# AKK_V3.net
KiCad netlist of a schematic drawn in Altium Designer
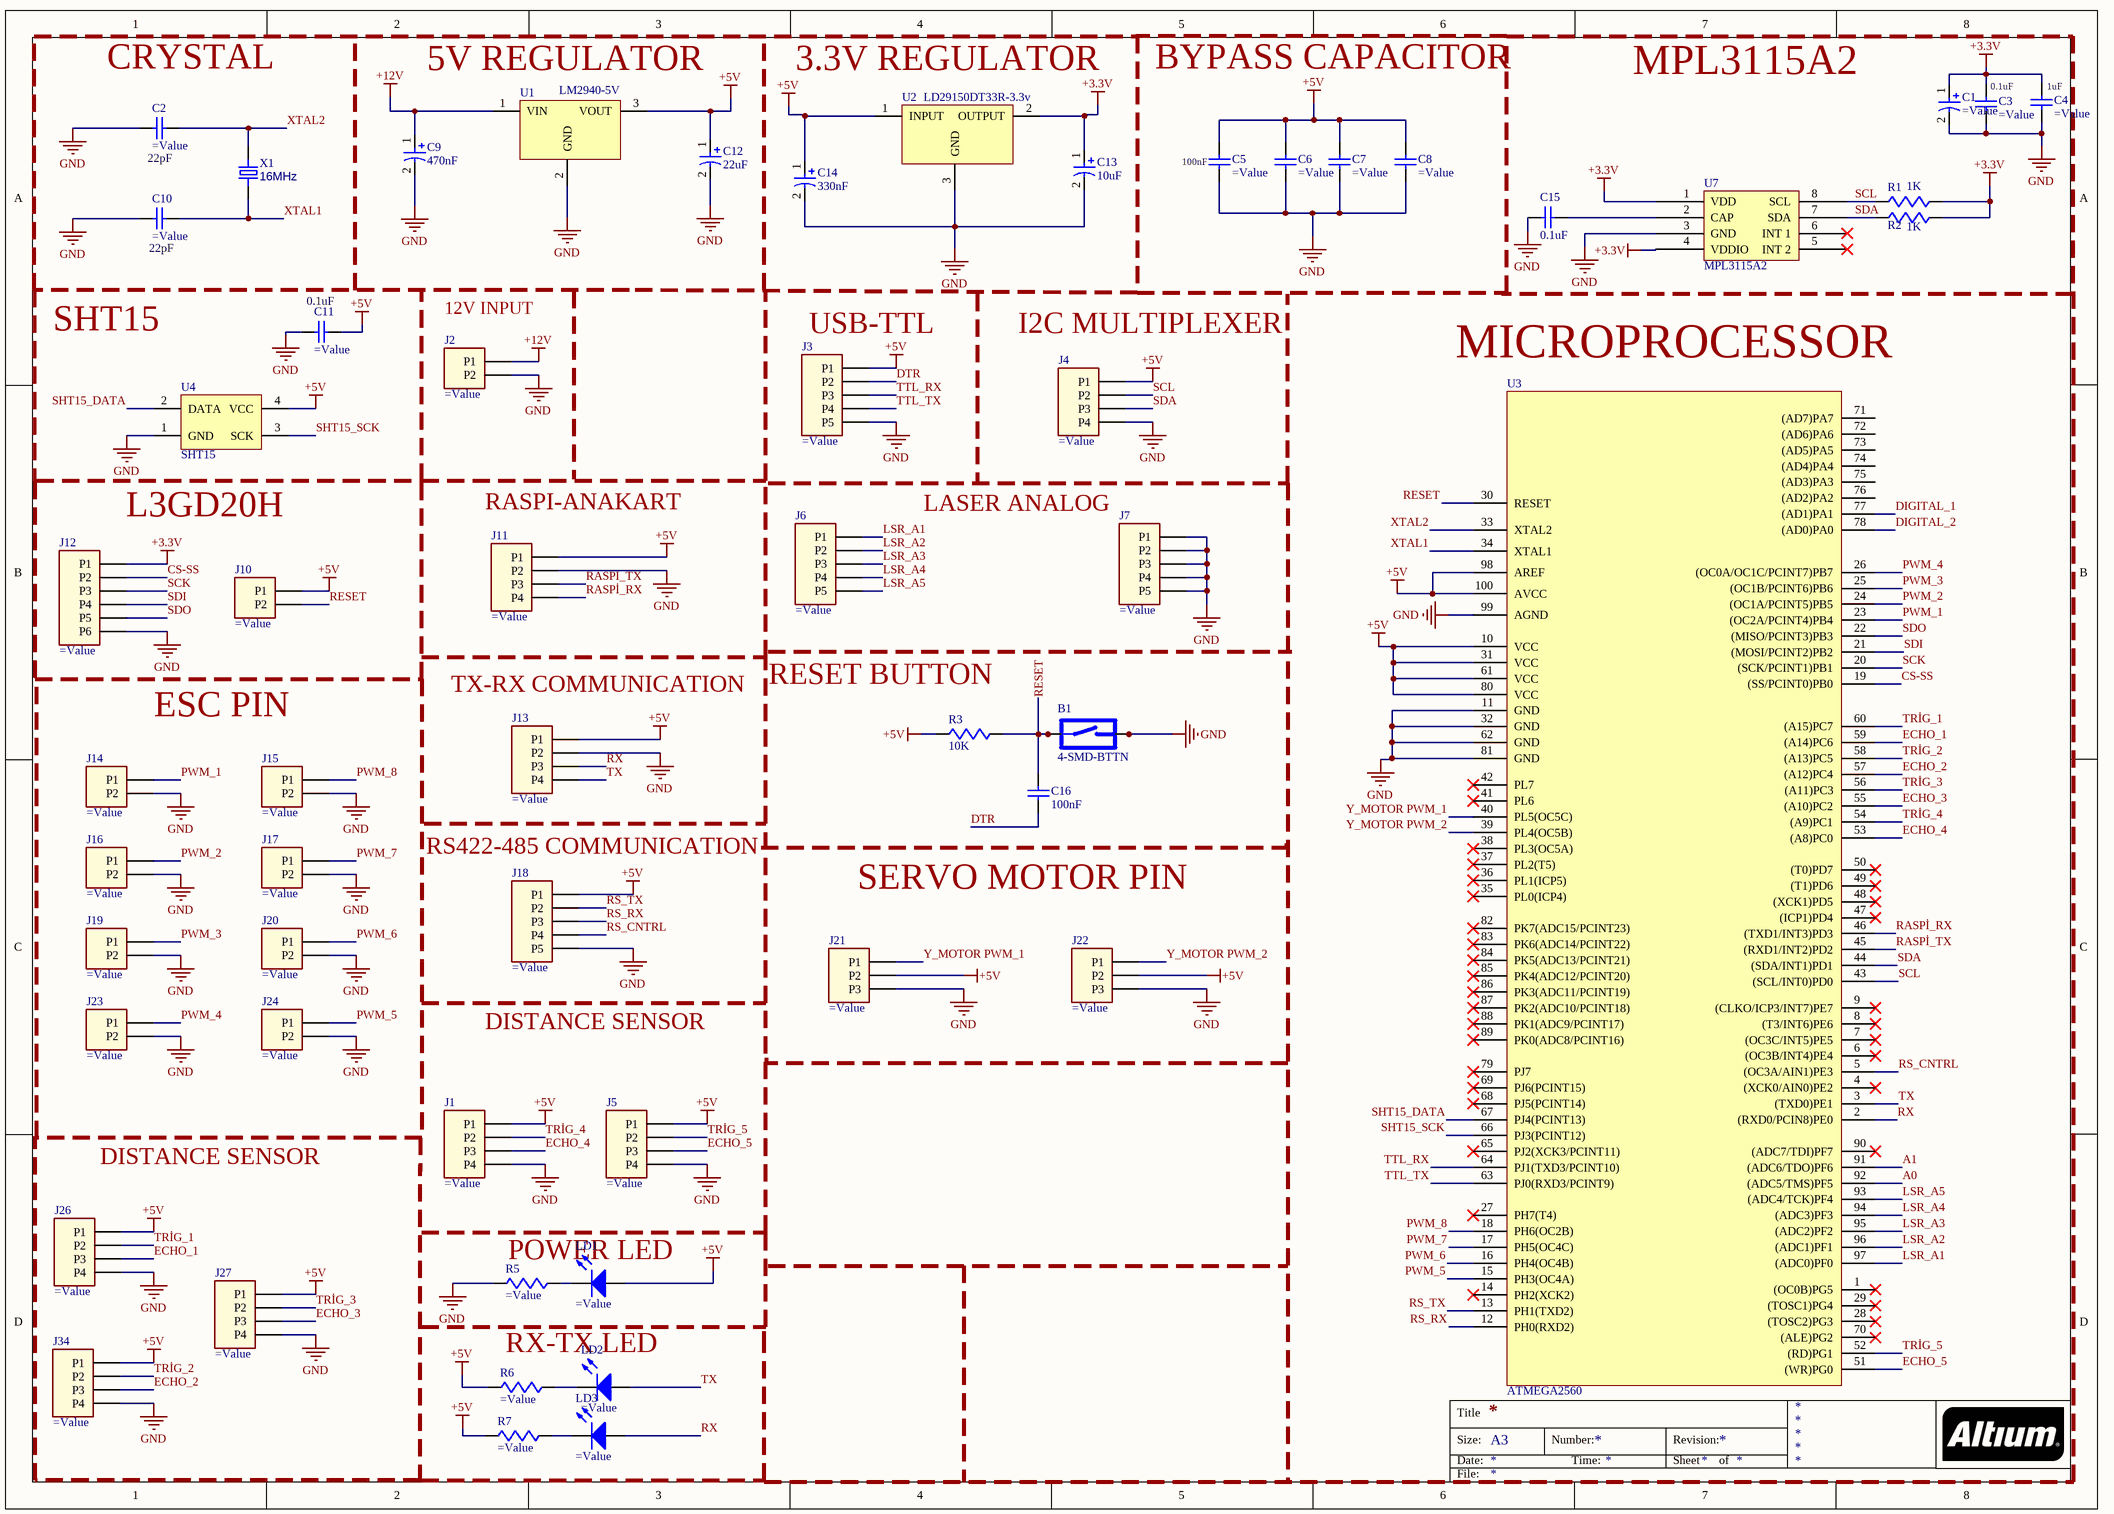
[diagram p0: AKK_V3.SchDoc]

(export (version "E")
  (design (tool "Eeschema 10.0.6"))
  (components
    (comp (ref "B1")
      (value "4-SMD-BTTN")
      (footprint "4-SMD-BTTN-11.6-6.5")
      (description "SWITCH TACTILE SPST-NO 0.05A 24V")
      (fields (field (name "MANUFACTURER PART NUMBER") "B3FS-1012P") (field (name "MANUFACTURER") "Omron"))
      (libsource (lib "MyDatabaseLib") (part "4-SMD-BTTN"))
    )
    (comp (ref "C1")
      (value "~")
      (footprint "CAP_5MM")
      (description "Capacitor; Alum Electrolytic; Cap 10 uF; Tol 20%; Vol-Rtg 16 VDC; SMT; 4x5.5; Cut Tape")
      (fields
        (field (name "MANUFACTURER PART NUMBER") "EEE-1CA100SR")
        (field (name "MANUFACTURER") "Panasonic")
      )
      (libsource (lib "MyDatabaseLib") (part "Capacitor POL"))
    )
    (comp (ref "C2")
      (value "~")
      (footprint "C1206N")
      (description "CAP CER 0.1UF 50V X7R 1206")
      (fields
        (field (name "MANUFACTURER PART NUMBER") "C1206C104K5RAC7210")
        (field (name "MANUFACTURER") "KEMET")
      )
      (libsource (lib "MyDatabaseLib") (part "CapacitorNonPol"))
    )
    (comp (ref "C3")
      (value "~")
      (footprint "C1206N")
      (description "CAP CER 0.1UF 50V X7R 1206")
      (fields
        (field (name "MANUFACTURER PART NUMBER") "C1206C104K5RAC7210")
        (field (name "MANUFACTURER") "KEMET")
      )
      (libsource (lib "MyDatabaseLib") (part "CapacitorNonPol"))
    )
    (comp (ref "C4")
      (value "~")
      (footprint "C1206N")
      (description "CAP CER 0.1UF 50V X7R 1206")
      (fields
        (field (name "MANUFACTURER PART NUMBER") "C1206C104K5RAC7210")
        (field (name "MANUFACTURER") "KEMET")
      )
      (libsource (lib "MyDatabaseLib") (part "CapacitorNonPol"))
    )
    (comp (ref "C5")
      (value "~")
      (footprint "C1206N")
      (description "CAP CER 0.1UF 50V X7R 1206")
      (fields
        (field (name "MANUFACTURER PART NUMBER") "C1206C104K5RAC7210")
        (field (name "MANUFACTURER") "KEMET")
      )
      (libsource (lib "MyDatabaseLib") (part "CapacitorNonPol"))
    )
    (comp (ref "C6")
      (value "~")
      (footprint "C1206N")
      (description "CAP CER 0.1UF 50V X7R 1206")
      (fields
        (field (name "MANUFACTURER PART NUMBER") "C1206C104K5RAC7210")
        (field (name "MANUFACTURER") "KEMET")
      )
      (libsource (lib "MyDatabaseLib") (part "CapacitorNonPol"))
    )
    (comp (ref "C7")
      (value "~")
      (footprint "C1206N")
      (description "CAP CER 0.1UF 50V X7R 1206")
      (fields
        (field (name "MANUFACTURER PART NUMBER") "C1206C104K5RAC7210")
        (field (name "MANUFACTURER") "KEMET")
      )
      (libsource (lib "MyDatabaseLib") (part "CapacitorNonPol"))
    )
    (comp (ref "C8")
      (value "~")
      (footprint "C1206N")
      (description "CAP CER 0.1UF 50V X7R 1206")
      (fields
        (field (name "MANUFACTURER PART NUMBER") "C1206C104K5RAC7210")
        (field (name "MANUFACTURER") "KEMET")
      )
      (libsource (lib "MyDatabaseLib") (part "CapacitorNonPol"))
    )
    (comp (ref "C9")
      (value "470nF")
      (footprint "T_1206")
      (description "CAP TANT POLY 10UF 20V 1206")
      (fields
        (field (name "MANUFACTURER PART NUMBER") "TCJA106M020R0150")
        (field (name "MANUFACTURER") "Kyocera AVX")
      )
      (libsource (lib "MyDatabaseLib") (part "Capacitor POL"))
    )
    (comp (ref "C10")
      (value "~")
      (footprint "C1206N")
      (description "CAP CER 0.1UF 50V X7R 1206")
      (fields
        (field (name "MANUFACTURER PART NUMBER") "C1206C104K5RAC7210")
        (field (name "MANUFACTURER") "KEMET")
      )
      (libsource (lib "MyDatabaseLib") (part "CapacitorNonPol"))
    )
    (comp (ref "C11")
      (value "~")
      (footprint "C1206N")
      (description "CAP CER 0.1UF 50V X7R 1206")
      (fields
        (field (name "MANUFACTURER PART NUMBER") "C1206C104K5RAC7210")
        (field (name "MANUFACTURER") "KEMET")
      )
      (libsource (lib "MyDatabaseLib") (part "CapacitorNonPol"))
    )
    (comp (ref "C12")
      (value "22uF")
      (footprint "T_7343")
      (description "CAP TANT POLY 22UF 35V 2917")
      (fields
        (field (name "MANUFACTURER PART NUMBER") "TCJD226M035R0100")
        (field (name "MANUFACTURER") "Kyocera AVX")
      )
      (libsource (lib "MyDatabaseLib") (part "Capacitor POL"))
    )
    (comp (ref "C13")
      (value "10uF")
      (footprint "T_7343")
      (description "CAP TANT POLY 22UF 35V 2917")
      (fields
        (field (name "MANUFACTURER PART NUMBER") "TCJD226M035R0100")
        (field (name "MANUFACTURER") "Kyocera AVX")
      )
      (libsource (lib "MyDatabaseLib") (part "Capacitor POL"))
    )
    (comp (ref "C14")
      (value "330nF")
      (footprint "T_1206")
      (description "CAP TANT POLY 10UF 20V 1206")
      (fields
        (field (name "MANUFACTURER PART NUMBER") "TCJA106M020R0150")
        (field (name "MANUFACTURER") "Kyocera AVX")
      )
      (libsource (lib "MyDatabaseLib") (part "Capacitor POL"))
    )
    (comp (ref "C15")
      (value "0.1uF")
      (footprint "C1206N")
      (description "CAP CER 0.1UF 50V X7R 1206")
      (fields
        (field (name "MANUFACTURER PART NUMBER") "C1206C104K5RAC7210")
        (field (name "MANUFACTURER") "KEMET")
      )
      (libsource (lib "MyDatabaseLib") (part "CapacitorNonPol"))
    )
    (comp (ref "C16")
      (value "100nF")
      (footprint "C1206N")
      (description "CAP CER 0.1UF 50V X7R 1206")
      (fields
        (field (name "MANUFACTURER PART NUMBER") "C1206C104K5RAC7210")
        (field (name "MANUFACTURER") "KEMET")
      )
      (libsource (lib "MyDatabaseLib") (part "CapacitorNonPol"))
    )
    (comp (ref "J1")
      (value "~")
      (footprint "4_PİN_HEADER")
      (description "CONN HDR 4POS 0.1 TIN PCB")
      (fields
        (field (name "MANUFACTURER PART NUMBER") "PPTC041LFBN-RC")
        (field (name "MANUFACTURER") "Sullins")
      )
      (libsource (lib "MyDatabaseLib") (part "CONN 4"))
    )
    (comp (ref "J2")
      (value "~")
      (footprint "Klemens_5mm")
      (description "Terminal Block Plug Female Socket 2 Position 5mm Screw Straight Cable Mount 15A")
      (fields
        (field (name "MANUFACTURER PART NUMBER") "OSTTH020160")
        (field (name "MANUFACTURER") "On-Shore Technology")
      )
      (libsource (lib "MyDatabaseLib") (part "CONN 2"))
    )
    (comp (ref "J3")
      (value "~")
      (footprint "5_PİN_HEADER")
      (description "CONN HDR 5POS 0.1 GOLD PCB")
      (fields
        (field (name "MANUFACTURER PART NUMBER") "PPPC051LFBN-RC")
        (field (name "MANUFACTURER") "Sullins")
      )
      (libsource (lib "MyDatabaseLib") (part "CONN 5"))
    )
    (comp (ref "J4")
      (value "~")
      (footprint "4_PİN_HEADER")
      (description "CONN HDR 4POS 0.1 TIN PCB")
      (fields
        (field (name "MANUFACTURER PART NUMBER") "PPTC041LFBN-RC")
        (field (name "MANUFACTURER") "Sullins")
      )
      (libsource (lib "MyDatabaseLib") (part "CONN 4"))
    )
    (comp (ref "J5")
      (value "~")
      (footprint "4_PİN_HEADER")
      (description "CONN HDR 4POS 0.1 TIN PCB")
      (fields
        (field (name "MANUFACTURER PART NUMBER") "PPTC041LFBN-RC")
        (field (name "MANUFACTURER") "Sullins")
      )
      (libsource (lib "MyDatabaseLib") (part "CONN 4"))
    )
    (comp (ref "J6")
      (value "~")
      (footprint "5_PİN_HEADER")
      (description "CONN HDR 5POS 0.1 GOLD PCB")
      (fields
        (field (name "MANUFACTURER PART NUMBER") "PPPC051LFBN-RC")
        (field (name "MANUFACTURER") "Sullins")
      )
      (libsource (lib "MyDatabaseLib") (part "CONN 5"))
    )
    (comp (ref "J7")
      (value "~")
      (footprint "5_PİN_HEADER")
      (description "CONN HDR 5POS 0.1 GOLD PCB")
      (fields
        (field (name "MANUFACTURER PART NUMBER") "PPPC051LFBN-RC")
        (field (name "MANUFACTURER") "Sullins")
      )
      (libsource (lib "MyDatabaseLib") (part "CONN 5"))
    )
    (comp (ref "J10")
      (value "~")
      (footprint "2_PİN_HEADER")
      (description "CONN HDR 2POS 0.1 TIN PCB")
      (fields
        (field (name "MANUFACTURER PART NUMBER") "PPTC021LFBN-RC")
        (field (name "MANUFACTURER") "Sullins")
      )
      (libsource (lib "MyDatabaseLib") (part "CONN 2"))
    )
    (comp (ref "J11")
      (value "~")
      (footprint "4_PİN_HEADER")
      (description "CONN HDR 4POS 0.1 TIN PCB")
      (fields
        (field (name "MANUFACTURER PART NUMBER") "PPTC041LFBN-RC")
        (field (name "MANUFACTURER") "Sullins")
      )
      (libsource (lib "MyDatabaseLib") (part "CONN 4"))
    )
    (comp (ref "J12")
      (value "~")
      (footprint "CONN_6_XH")
      (description "Pin header, single-row straight 6-pin 2.5 mm Pole no. 6 XH, B6B-XH-A, JST")
      (fields (field (name "MANUFACTURER PART NUMBER") "B6B-XH-A") (field (name "MANUFACTURER") "JST"))
      (libsource (lib "MyDatabaseLib") (part "CONN 6"))
    )
    (comp (ref "J13")
      (value "~")
      (footprint "4_PİN_HEADER")
      (description "CONN HDR 4POS 0.1 TIN PCB")
      (fields
        (field (name "MANUFACTURER PART NUMBER") "PPTC041LFBN-RC")
        (field (name "MANUFACTURER") "Sullins")
      )
      (libsource (lib "MyDatabaseLib") (part "CONN 4"))
    )
    (comp (ref "J14")
      (value "~")
      (footprint "CONN_2_XH")
      (fields (field (name "MANUFACTURER PART NUMBER") "B2P-VH(LF)(SN)") (field (name "MANUFACTURER") "JST"))
      (libsource (lib "MyDatabaseLib") (part "CONN 2"))
    )
    (comp (ref "J15")
      (value "~")
      (footprint "CONN_2_XH")
      (fields (field (name "MANUFACTURER PART NUMBER") "B2P-VH(LF)(SN)") (field (name "MANUFACTURER") "JST"))
      (libsource (lib "MyDatabaseLib") (part "CONN 2"))
    )
    (comp (ref "J16")
      (value "~")
      (footprint "CONN_2_XH")
      (fields (field (name "MANUFACTURER PART NUMBER") "B2P-VH(LF)(SN)") (field (name "MANUFACTURER") "JST"))
      (libsource (lib "MyDatabaseLib") (part "CONN 2"))
    )
    (comp (ref "J17")
      (value "~")
      (footprint "CONN_2_XH")
      (fields (field (name "MANUFACTURER PART NUMBER") "B2P-VH(LF)(SN)") (field (name "MANUFACTURER") "JST"))
      (libsource (lib "MyDatabaseLib") (part "CONN 2"))
    )
    (comp (ref "J18")
      (value "~")
      (footprint "5_PİN_HEADER")
      (description "CONN HDR 5POS 0.1 GOLD PCB")
      (fields
        (field (name "MANUFACTURER PART NUMBER") "PPPC051LFBN-RC")
        (field (name "MANUFACTURER") "Sullins")
      )
      (libsource (lib "MyDatabaseLib") (part "CONN 5"))
    )
    (comp (ref "J19")
      (value "~")
      (footprint "CONN_2_XH")
      (fields (field (name "MANUFACTURER PART NUMBER") "B2P-VH(LF)(SN)") (field (name "MANUFACTURER") "JST"))
      (libsource (lib "MyDatabaseLib") (part "CONN 2"))
    )
    (comp (ref "J20")
      (value "~")
      (footprint "CONN_2_XH")
      (fields (field (name "MANUFACTURER PART NUMBER") "B2P-VH(LF)(SN)") (field (name "MANUFACTURER") "JST"))
      (libsource (lib "MyDatabaseLib") (part "CONN 2"))
    )
    (comp (ref "J21")
      (value "~")
      (footprint "CONN_3_XH")
      (description "03P MTA100 SHRD HDR,W/O PEG SN")
      (fields
        (field (name "MANUFACTURER PART NUMBER") "2-644861-3")
        (field (name "MANUFACTURER") "TE Connectivity")
      )
      (libsource (lib "MyDatabaseLib") (part "CONN 3"))
    )
    (comp (ref "J22")
      (value "~")
      (footprint "CONN_3_XH")
      (description "03P MTA100 SHRD HDR,W/O PEG SN")
      (fields
        (field (name "MANUFACTURER PART NUMBER") "2-644861-3")
        (field (name "MANUFACTURER") "TE Connectivity")
      )
      (libsource (lib "MyDatabaseLib") (part "CONN 3"))
    )
    (comp (ref "J23")
      (value "~")
      (footprint "CONN_2_XH")
      (fields (field (name "MANUFACTURER PART NUMBER") "B2P-VH(LF)(SN)") (field (name "MANUFACTURER") "JST"))
      (libsource (lib "MyDatabaseLib") (part "CONN 2"))
    )
    (comp (ref "J24")
      (value "~")
      (footprint "CONN_2_XH")
      (fields (field (name "MANUFACTURER PART NUMBER") "B2P-VH(LF)(SN)") (field (name "MANUFACTURER") "JST"))
      (libsource (lib "MyDatabaseLib") (part "CONN 2"))
    )
    (comp (ref "J26")
      (value "~")
      (footprint "4_PİN_HEADER")
      (description "CONN HDR 4POS 0.1 TIN PCB")
      (fields
        (field (name "MANUFACTURER PART NUMBER") "PPTC041LFBN-RC")
        (field (name "MANUFACTURER") "Sullins")
      )
      (libsource (lib "MyDatabaseLib") (part "CONN 4"))
    )
    (comp (ref "J27")
      (value "~")
      (footprint "4_PİN_HEADER")
      (description "CONN HDR 4POS 0.1 TIN PCB")
      (fields
        (field (name "MANUFACTURER PART NUMBER") "PPTC041LFBN-RC")
        (field (name "MANUFACTURER") "Sullins")
      )
      (libsource (lib "MyDatabaseLib") (part "CONN 4"))
    )
    (comp (ref "J34")
      (value "~")
      (footprint "4_PİN_HEADER")
      (description "CONN HDR 4POS 0.1 TIN PCB")
      (fields
        (field (name "MANUFACTURER PART NUMBER") "PPTC041LFBN-RC")
        (field (name "MANUFACTURER") "Sullins")
      )
      (libsource (lib "MyDatabaseLib") (part "CONN 4"))
    )
    (comp (ref "LD1")
      (value "~")
      (footprint "1206-BLUE")
      (description "LED BLUE CLEAR 1206 SMD")
      (fields
        (field (name "MANUFACTURER PART NUMBER") "APTR3216PBC/A")
        (field (name "MANUFACTURER") "Kingbright")
      )
      (libsource (lib "MyDatabaseLib") (part "LED"))
    )
    (comp (ref "LD2")
      (value "~")
      (footprint "1206-BLUE")
      (description "LED BLUE CLEAR 1206 SMD")
      (fields
        (field (name "MANUFACTURER PART NUMBER") "APTR3216PBC/A")
        (field (name "MANUFACTURER") "Kingbright")
      )
      (libsource (lib "MyDatabaseLib") (part "LED"))
    )
    (comp (ref "LD3")
      (value "~")
      (footprint "1206-BLUE")
      (description "LED BLUE CLEAR 1206 SMD")
      (fields
        (field (name "MANUFACTURER PART NUMBER") "APTR3216PBC/A")
        (field (name "MANUFACTURER") "Kingbright")
      )
      (libsource (lib "MyDatabaseLib") (part "LED"))
    )
    (comp (ref "R1")
      (value "1K")
      (footprint "R1206N")
      (description "RES SMD 1K OHM 0.1% 1W 1206")
      (fields
        (field (name "MANUFACTURER PART NUMBER") "HRG3216P-1001-B-T1")
        (field (name "MANUFACTURER") "Susumu")
      )
      (libsource (lib "MyDatabaseLib") (part "Resistor"))
    )
    (comp (ref "R2")
      (value "1K")
      (footprint "R1206N")
      (description "RES SMD 1K OHM 0.1% 1W 1206")
      (fields
        (field (name "MANUFACTURER PART NUMBER") "HRG3216P-1001-B-T1")
        (field (name "MANUFACTURER") "Susumu")
      )
      (libsource (lib "MyDatabaseLib") (part "Resistor"))
    )
    (comp (ref "R3")
      (value "10K")
      (footprint "R1206N")
      (description "RES SMD 1K OHM 0.1% 1W 1206")
      (fields
        (field (name "MANUFACTURER PART NUMBER") "HRG3216P-1001-B-T1")
        (field (name "MANUFACTURER") "Susumu")
      )
      (libsource (lib "MyDatabaseLib") (part "Resistor"))
    )
    (comp (ref "R5")
      (value "~")
      (footprint "R1206N")
      (description "RES SMD 1K OHM 0.1% 1W 1206")
      (fields
        (field (name "MANUFACTURER PART NUMBER") "HRG3216P-1001-B-T1")
        (field (name "MANUFACTURER") "Susumu")
      )
      (libsource (lib "MyDatabaseLib") (part "Resistor"))
    )
    (comp (ref "R6")
      (value "~")
      (footprint "R1206N")
      (description "RES SMD 1K OHM 0.1% 1W 1206")
      (fields
        (field (name "MANUFACTURER PART NUMBER") "HRG3216P-1001-B-T1")
        (field (name "MANUFACTURER") "Susumu")
      )
      (libsource (lib "MyDatabaseLib") (part "Resistor"))
    )
    (comp (ref "R7")
      (value "~")
      (footprint "R1206N")
      (description "RES SMD 1K OHM 0.1% 1W 1206")
      (fields
        (field (name "MANUFACTURER PART NUMBER") "HRG3216P-1001-B-T1")
        (field (name "MANUFACTURER") "Susumu")
      )
      (libsource (lib "MyDatabaseLib") (part "Resistor"))
    )
    (comp (ref "U1")
      (value "LM2940-5V")
      (footprint "TO220")
      (fields
        (field (name "MANUFACTURER PART NUMBER") "LM2940T-5.0/NOPB")
        (field (name "MANUFACTURER") "TI National Semiconductor")
        (field (name "VOLTAGE") "5V")
      )
      (libsource (lib "MyDatabaseLib") (part "LM2940-5V"))
    )
    (comp (ref "U2")
      (value "LD29150DT33R-3.3v")
      (footprint "TO252-DPAK")
      (fields
        (field (name "MANUFACTURER PART NUMBER") "LD29150DT33R")
        (field (name "MANUFACTURER") "STMicroelectronics")
      )
      (libsource (lib "MyDatabaseLib") (part "LD29150DT33R-3.3v"))
    )
    (comp (ref "U3")
      (value "ATMEGA2560")
      (footprint "TQFP100-2")
      (fields (field (name "MANUFACTURER PART NUMBER") "ATMEGA2560-16AU"))
      (libsource (lib "MyDatabaseLib") (part "ATMEGA2560"))
    )
    (comp (ref "U4")
      (value "SHT15")
      (footprint "SHT15")
      (description "SENSIRION - SHT15 - SENSOR, HUMIDITY & TEMP, 3.3V")
      (fields (field (name "MANUFACTURER") "Sensirion"))
      (libsource (lib "MyDatabaseLib") (part "SHT15"))
    )
    (comp (ref "U7")
      (value "MPL3115A2")
      (footprint "MPL3115A2")
      (libsource (lib "MPL3115A2") (part "MPL3115A2"))
    )
    (comp (ref "X1")
      (value "16MHz")
      (footprint "HC49")
      (description "Crystal 25MHz ±30ppm (Tol) ±50ppm (Stability) 20pF 2-Pin HC-49/SDLF SMD T/R")
      (fields
        (field (name "MANUFACTURER PART NUMBER") "FC4SDCBMF25.0-T1")
        (field (name "MANUFACTURER") "Fox Electronics")
      )
      (libsource (lib "MyDatabaseLib") (part "XTAL"))
    )
  )
  (nets
    (net (code "1") (name "+3.3V") (class "Default")
      (node (ref "C1") (pin "1") (pinfunction "P_1") (pintype "passive"))
      (node (ref "C13") (pin "1") (pinfunction "P_1") (pintype "passive"))
      (node (ref "C3") (pin "2") (pinfunction "2_2") (pintype "passive"))
      (node (ref "C4") (pin "2") (pinfunction "2_2") (pintype "passive"))
      (node (ref "J12") (pin "1") (pinfunction "P1_1") (pintype "passive"))
      (node (ref "R1") (pin "2") (pinfunction "B_2") (pintype "passive"))
      (node (ref "R2") (pin "2") (pinfunction "B_2") (pintype "passive"))
      (node (ref "U2") (pin "2") (pinfunction "OUTPUT_2") (pintype "passive"))
      (node (ref "U7") (pin "1") (pinfunction "VDD_1") (pintype "passive"))
      (node (ref "U7") (pin "4") (pinfunction "VDDIO_4") (pintype "passive"))
    )
    (net (code "2") (name "+5V") (class "Default")
      (node (ref "C11") (pin "1") (pinfunction "1_1") (pintype "passive"))
      (node (ref "C12") (pin "1") (pinfunction "P_1") (pintype "passive"))
      (node (ref "C14") (pin "1") (pinfunction "P_1") (pintype "passive"))
      (node (ref "C5") (pin "2") (pinfunction "2_2") (pintype "passive"))
      (node (ref "C6") (pin "2") (pinfunction "2_2") (pintype "passive"))
      (node (ref "C7") (pin "2") (pinfunction "2_2") (pintype "passive"))
      (node (ref "C8") (pin "2") (pinfunction "2_2") (pintype "passive"))
      (node (ref "J1") (pin "1") (pinfunction "P1_1") (pintype "passive"))
      (node (ref "J10") (pin "1") (pinfunction "P1_1") (pintype "passive"))
      (node (ref "J11") (pin "1") (pinfunction "P1_1") (pintype "passive"))
      (node (ref "J13") (pin "1") (pinfunction "P1_1") (pintype "passive"))
      (node (ref "J18") (pin "1") (pinfunction "P1_1") (pintype "passive"))
      (node (ref "J21") (pin "2") (pinfunction "P2_2") (pintype "passive"))
      (node (ref "J22") (pin "2") (pinfunction "P2_2") (pintype "passive"))
      (node (ref "J26") (pin "1") (pinfunction "P1_1") (pintype "passive"))
      (node (ref "J27") (pin "1") (pinfunction "P1_1") (pintype "passive"))
      (node (ref "J3") (pin "1") (pinfunction "P1_1") (pintype "passive"))
      (node (ref "J34") (pin "1") (pinfunction "P1_1") (pintype "passive"))
      (node (ref "J4") (pin "1") (pinfunction "P1_1") (pintype "passive"))
      (node (ref "J5") (pin "1") (pinfunction "P1_1") (pintype "passive"))
      (node (ref "LD1") (pin "2") (pinfunction "A_2") (pintype "passive"))
      (node (ref "R3") (pin "1") (pinfunction "A_1") (pintype "passive"))
      (node (ref "R6") (pin "1") (pinfunction "A_1") (pintype "passive"))
      (node (ref "R7") (pin "1") (pinfunction "A_1") (pintype "passive"))
      (node (ref "U1") (pin "3") (pinfunction "VOUT_3") (pintype "passive"))
      (node (ref "U2") (pin "1") (pinfunction "INPUT_1") (pintype "passive"))
      (node (ref "U3") (pin "10") (pinfunction "VCC_10") (pintype "passive"))
      (node (ref "U3") (pin "100") (pinfunction "AVCC_100") (pintype "passive"))
      (node (ref "U3") (pin "31") (pinfunction "VCC_31") (pintype "passive"))
      (node (ref "U3") (pin "61") (pinfunction "VCC_61") (pintype "passive"))
      (node (ref "U3") (pin "80") (pinfunction "VCC_80") (pintype "passive"))
      (node (ref "U3") (pin "98") (pinfunction "AREF_98") (pintype "passive"))
      (node (ref "U4") (pin "4") (pinfunction "VCC_4") (pintype "passive"))
    )
    (net (code "3") (name "+12V") (class "Default")
      (node (ref "C9") (pin "1") (pinfunction "P_1") (pintype "passive"))
      (node (ref "J2") (pin "1") (pinfunction "P1_1") (pintype "passive"))
      (node (ref "U1") (pin "1") (pinfunction "VIN_1") (pintype "passive"))
    )
    (net (code "4") (name "/A0") (class "Default")
      (node (ref "U3") (pin "92") (pinfunction "(ADC5/TMS)PF5_92") (pintype "passive"))
    )
    (net (code "5") (name "/A1") (class "Default")
      (node (ref "U3") (pin "91") (pinfunction "(ADC6/TDO)PF6_91") (pintype "passive"))
    )
    (net (code "6") (name "/CS-SS") (class "Default")
      (node (ref "J12") (pin "2") (pinfunction "P2_2") (pintype "passive"))
      (node (ref "U3") (pin "19") (pinfunction "(SS/PCINT0)PB0_19") (pintype "passive"))
    )
    (net (code "7") (name "/DIGITAL_1") (class "Default")
      (node (ref "U3") (pin "77") (pinfunction "(AD1)PA1_77") (pintype "passive"))
    )
    (net (code "8") (name "/DIGITAL_2") (class "Default")
      (node (ref "U3") (pin "78") (pinfunction "(AD0)PA0_78") (pintype "passive"))
    )
    (net (code "9") (name "/DTR") (class "Default")
      (node (ref "C16") (pin "1") (pinfunction "1_1") (pintype "passive"))
      (node (ref "J3") (pin "2") (pinfunction "P2_2") (pintype "passive"))
    )
    (net (code "10") (name "/ECHO_1") (class "Default")
      (node (ref "J26") (pin "3") (pinfunction "P3_3") (pintype "passive"))
      (node (ref "U3") (pin "59") (pinfunction "(A14)PC6_59") (pintype "passive"))
    )
    (net (code "11") (name "/ECHO_2") (class "Default")
      (node (ref "J34") (pin "3") (pinfunction "P3_3") (pintype "passive"))
      (node (ref "U3") (pin "57") (pinfunction "(A12)PC4_57") (pintype "passive"))
    )
    (net (code "12") (name "/ECHO_3") (class "Default")
      (node (ref "J27") (pin "3") (pinfunction "P3_3") (pintype "passive"))
      (node (ref "U3") (pin "55") (pinfunction "(A10)PC2_55") (pintype "passive"))
    )
    (net (code "13") (name "/ECHO_4") (class "Default")
      (node (ref "J1") (pin "3") (pinfunction "P3_3") (pintype "passive"))
      (node (ref "U3") (pin "53") (pinfunction "(A8)PC0_53") (pintype "passive"))
    )
    (net (code "14") (name "/ECHO_5") (class "Default")
      (node (ref "J5") (pin "3") (pinfunction "P3_3") (pintype "passive"))
      (node (ref "U3") (pin "51") (pinfunction "(WR)PG0_51") (pintype "passive"))
    )
    (net (code "15") (name "/LSR_A1") (class "Default")
      (node (ref "J6") (pin "1") (pinfunction "P1_1") (pintype "passive"))
      (node (ref "U3") (pin "97") (pinfunction "(ADC0)PF0_97") (pintype "passive"))
    )
    (net (code "16") (name "/LSR_A2") (class "Default")
      (node (ref "J6") (pin "2") (pinfunction "P2_2") (pintype "passive"))
      (node (ref "U3") (pin "96") (pinfunction "(ADC1)PF1_96") (pintype "passive"))
    )
    (net (code "17") (name "/LSR_A3") (class "Default")
      (node (ref "J6") (pin "3") (pinfunction "P3_3") (pintype "passive"))
      (node (ref "U3") (pin "95") (pinfunction "(ADC2)PF2_95") (pintype "passive"))
    )
    (net (code "18") (name "/LSR_A4") (class "Default")
      (node (ref "J6") (pin "4") (pinfunction "P4_4") (pintype "passive"))
      (node (ref "U3") (pin "94") (pinfunction "(ADC3)PF3_94") (pintype "passive"))
    )
    (net (code "19") (name "/LSR_A5") (class "Default")
      (node (ref "J6") (pin "5") (pinfunction "P5_5") (pintype "passive"))
      (node (ref "U3") (pin "93") (pinfunction "(ADC4/TCK)PF4_93") (pintype "passive"))
    )
    (net (code "20") (name "/PWM_1") (class "Default")
      (node (ref "J14") (pin "1") (pinfunction "P1_1") (pintype "passive"))
      (node (ref "U3") (pin "23") (pinfunction "(OC2A/PCINT4)PB4_23") (pintype "passive"))
    )
    (net (code "21") (name "/PWM_2") (class "Default")
      (node (ref "J16") (pin "1") (pinfunction "P1_1") (pintype "passive"))
      (node (ref "U3") (pin "24") (pinfunction "(OC1A/PCINT5)PB5_24") (pintype "passive"))
    )
    (net (code "22") (name "/PWM_3") (class "Default")
      (node (ref "J19") (pin "1") (pinfunction "P1_1") (pintype "passive"))
      (node (ref "U3") (pin "25") (pinfunction "(OC1B/PCINT6)PB6_25") (pintype "passive"))
    )
    (net (code "23") (name "/PWM_4") (class "Default")
      (node (ref "J23") (pin "1") (pinfunction "P1_1") (pintype "passive"))
      (node (ref "U3") (pin "26") (pinfunction "(OC0A/OC1C/PCINT7)PB7_26") (pintype "passive"))
    )
    (net (code "24") (name "/PWM_5") (class "Default")
      (node (ref "J24") (pin "1") (pinfunction "P1_1") (pintype "passive"))
      (node (ref "U3") (pin "15") (pinfunction "PH3(OC4A)_15") (pintype "passive"))
    )
    (net (code "25") (name "/PWM_6") (class "Default")
      (node (ref "J20") (pin "1") (pinfunction "P1_1") (pintype "passive"))
      (node (ref "U3") (pin "16") (pinfunction "PH4(OC4B)_16") (pintype "passive"))
    )
    (net (code "26") (name "/PWM_7") (class "Default")
      (node (ref "J17") (pin "1") (pinfunction "P1_1") (pintype "passive"))
      (node (ref "U3") (pin "17") (pinfunction "PH5(OC4C)_17") (pintype "passive"))
    )
    (net (code "27") (name "/PWM_8") (class "Default")
      (node (ref "J15") (pin "1") (pinfunction "P1_1") (pintype "passive"))
      (node (ref "U3") (pin "18") (pinfunction "PH6(OC2B)_18") (pintype "passive"))
    )
    (net (code "28") (name "/RASPİ_RX") (class "Default")
      (node (ref "J11") (pin "4") (pinfunction "P4_4") (pintype "passive"))
      (node (ref "U3") (pin "46") (pinfunction "(TXD1/INT3)PD3_46") (pintype "passive"))
    )
    (net (code "29") (name "/RASPİ_TX") (class "Default")
      (node (ref "J11") (pin "3") (pinfunction "P3_3") (pintype "passive"))
      (node (ref "U3") (pin "45") (pinfunction "(RXD1/INT2)PD2_45") (pintype "passive"))
    )
    (net (code "30") (name "/RESET") (class "Default")
      (node (ref "B1") (pin "3") (pinfunction "1_3") (pintype "passive"))
      (node (ref "B1") (pin "4") (pinfunction "1_4") (pintype "passive"))
      (node (ref "C16") (pin "2") (pinfunction "2_2") (pintype "passive"))
      (node (ref "J10") (pin "2") (pinfunction "P2_2") (pintype "passive"))
      (node (ref "R3") (pin "2") (pinfunction "B_2") (pintype "passive"))
      (node (ref "U3") (pin "30") (pinfunction "RESET_30") (pintype "passive"))
    )
    (net (code "31") (name "/RS_CNTRL") (class "Default")
      (node (ref "J18") (pin "4") (pinfunction "P4_4") (pintype "passive"))
      (node (ref "U3") (pin "5") (pinfunction "(OC3A/AIN1)PE3_5") (pintype "passive"))
    )
    (net (code "32") (name "/RS_RX") (class "Default")
      (node (ref "J18") (pin "3") (pinfunction "P3_3") (pintype "passive"))
      (node (ref "U3") (pin "12") (pinfunction "PH0(RXD2)_12") (pintype "passive"))
    )
    (net (code "33") (name "/RS_TX") (class "Default")
      (node (ref "J18") (pin "2") (pinfunction "P2_2") (pintype "passive"))
      (node (ref "U3") (pin "13") (pinfunction "PH1(TXD2)_13") (pintype "passive"))
    )
    (net (code "34") (name "/RX") (class "Default")
      (node (ref "J13") (pin "3") (pinfunction "P3_3") (pintype "passive"))
      (node (ref "LD3") (pin "2") (pinfunction "A_2") (pintype "passive"))
      (node (ref "U3") (pin "2") (pinfunction "(RXD0/PCIN8)PE0_2") (pintype "passive"))
    )
    (net (code "35") (name "/SCK") (class "Default")
      (node (ref "J12") (pin "3") (pinfunction "P3_3") (pintype "passive"))
      (node (ref "U3") (pin "20") (pinfunction "(SCK/PCINT1)PB1_20") (pintype "passive"))
    )
    (net (code "36") (name "/SCL") (class "Default")
      (node (ref "J4") (pin "2") (pinfunction "P2_2") (pintype "passive"))
      (node (ref "R1") (pin "1") (pinfunction "A_1") (pintype "passive"))
      (node (ref "U3") (pin "43") (pinfunction "(SCL/INT0)PD0_43") (pintype "passive"))
      (node (ref "U7") (pin "8") (pinfunction "SCL_8") (pintype "passive"))
    )
    (net (code "37") (name "/SDA") (class "Default")
      (node (ref "J4") (pin "3") (pinfunction "P3_3") (pintype "passive"))
      (node (ref "R2") (pin "1") (pinfunction "A_1") (pintype "passive"))
      (node (ref "U3") (pin "44") (pinfunction "(SDA/INT1)PD1_44") (pintype "passive"))
      (node (ref "U7") (pin "7") (pinfunction "SDA_7") (pintype "passive"))
    )
    (net (code "38") (name "/SDI") (class "Default")
      (node (ref "J12") (pin "4") (pinfunction "P4_4") (pintype "passive"))
      (node (ref "U3") (pin "21") (pinfunction "(MOSI/PCINT2)PB2_21") (pintype "passive"))
    )
    (net (code "39") (name "/SDO") (class "Default")
      (node (ref "J12") (pin "5") (pinfunction "P5_5") (pintype "passive"))
      (node (ref "U3") (pin "22") (pinfunction "(MISO/PCINT3)PB3_22") (pintype "passive"))
    )
    (net (code "40") (name "/SHT15_DATA") (class "Default")
      (node (ref "U3") (pin "67") (pinfunction "PJ4(PCINT13)_67") (pintype "passive"))
      (node (ref "U4") (pin "2") (pinfunction "DATA_2") (pintype "passive"))
    )
    (net (code "41") (name "/SHT15_SCK") (class "Default")
      (node (ref "U3") (pin "66") (pinfunction "PJ3(PCINT12)_66") (pintype "passive"))
      (node (ref "U4") (pin "3") (pinfunction "SCK_3") (pintype "passive"))
    )
    (net (code "42") (name "/TRİG_1") (class "Default")
      (node (ref "J26") (pin "2") (pinfunction "P2_2") (pintype "passive"))
      (node (ref "U3") (pin "60") (pinfunction "(A15)PC7_60") (pintype "passive"))
    )
    (net (code "43") (name "/TRİG_2") (class "Default")
      (node (ref "J34") (pin "2") (pinfunction "P2_2") (pintype "passive"))
      (node (ref "U3") (pin "58") (pinfunction "(A13)PC5_58") (pintype "passive"))
    )
    (net (code "44") (name "/TRİG_3") (class "Default")
      (node (ref "J27") (pin "2") (pinfunction "P2_2") (pintype "passive"))
      (node (ref "U3") (pin "56") (pinfunction "(A11)PC3_56") (pintype "passive"))
    )
    (net (code "45") (name "/TRİG_4") (class "Default")
      (node (ref "J1") (pin "2") (pinfunction "P2_2") (pintype "passive"))
      (node (ref "U3") (pin "54") (pinfunction "(A9)PC1_54") (pintype "passive"))
    )
    (net (code "46") (name "/TRİG_5") (class "Default")
      (node (ref "J5") (pin "2") (pinfunction "P2_2") (pintype "passive"))
      (node (ref "U3") (pin "52") (pinfunction "(RD)PG1_52") (pintype "passive"))
    )
    (net (code "47") (name "/TTL_RX") (class "Default")
      (node (ref "J3") (pin "3") (pinfunction "P3_3") (pintype "passive"))
      (node (ref "U3") (pin "64") (pinfunction "PJ1(TXD3/PCINT10)_64") (pintype "passive"))
    )
    (net (code "48") (name "/TTL_TX") (class "Default")
      (node (ref "J3") (pin "4") (pinfunction "P4_4") (pintype "passive"))
      (node (ref "U3") (pin "63") (pinfunction "PJ0(RXD3/PCINT9)_63") (pintype "passive"))
    )
    (net (code "49") (name "/TX") (class "Default")
      (node (ref "J13") (pin "4") (pinfunction "P4_4") (pintype "passive"))
      (node (ref "LD2") (pin "2") (pinfunction "A_2") (pintype "passive"))
      (node (ref "U3") (pin "3") (pinfunction "(TXD0)PE1_3") (pintype "passive"))
    )
    (net (code "50") (name "/XTAL1") (class "Default")
      (node (ref "C10") (pin "1") (pinfunction "1_1") (pintype "passive"))
      (node (ref "U3") (pin "34") (pinfunction "XTAL1_34") (pintype "passive"))
      (node (ref "X1") (pin "1") (pinfunction "1_1") (pintype "passive"))
    )
    (net (code "51") (name "/XTAL2") (class "Default")
      (node (ref "C2") (pin "1") (pinfunction "1_1") (pintype "passive"))
      (node (ref "U3") (pin "33") (pinfunction "XTAL2_33") (pintype "passive"))
      (node (ref "X1") (pin "2") (pinfunction "2_2") (pintype "passive"))
    )
    (net (code "52") (name "/Y_MOTOR PWM_1") (class "Default")
      (node (ref "J21") (pin "1") (pinfunction "P1_1") (pintype "passive"))
      (node (ref "U3") (pin "40") (pinfunction "PL5(OC5C)_40") (pintype "passive"))
    )
    (net (code "53") (name "/Y_MOTOR PWM_2") (class "Default")
      (node (ref "J22") (pin "1") (pinfunction "P1_1") (pintype "passive"))
      (node (ref "U3") (pin "39") (pinfunction "PL4(OC5B)_39") (pintype "passive"))
    )
    (net (code "54") (name "GND") (class "Default")
      (node (ref "B1") (pin "1") (pinfunction "2_1") (pintype "passive"))
      (node (ref "B1") (pin "2") (pinfunction "2_2") (pintype "passive"))
      (node (ref "C1") (pin "2") (pinfunction "N_2") (pintype "passive"))
      (node (ref "C10") (pin "2") (pinfunction "2_2") (pintype "passive"))
      (node (ref "C11") (pin "2") (pinfunction "2_2") (pintype "passive"))
      (node (ref "C12") (pin "2") (pinfunction "N_2") (pintype "passive"))
      (node (ref "C13") (pin "2") (pinfunction "N_2") (pintype "passive"))
      (node (ref "C14") (pin "2") (pinfunction "N_2") (pintype "passive"))
      (node (ref "C15") (pin "2") (pinfunction "2_2") (pintype "passive"))
      (node (ref "C2") (pin "2") (pinfunction "2_2") (pintype "passive"))
      (node (ref "C3") (pin "1") (pinfunction "1_1") (pintype "passive"))
      (node (ref "C4") (pin "1") (pinfunction "1_1") (pintype "passive"))
      (node (ref "C5") (pin "1") (pinfunction "1_1") (pintype "passive"))
      (node (ref "C6") (pin "1") (pinfunction "1_1") (pintype "passive"))
      (node (ref "C7") (pin "1") (pinfunction "1_1") (pintype "passive"))
      (node (ref "C8") (pin "1") (pinfunction "1_1") (pintype "passive"))
      (node (ref "C9") (pin "2") (pinfunction "N_2") (pintype "passive"))
      (node (ref "J1") (pin "4") (pinfunction "P4_4") (pintype "passive"))
      (node (ref "J11") (pin "2") (pinfunction "P2_2") (pintype "passive"))
      (node (ref "J12") (pin "6") (pinfunction "P6_6") (pintype "passive"))
      (node (ref "J13") (pin "2") (pinfunction "P2_2") (pintype "passive"))
      (node (ref "J14") (pin "2") (pinfunction "P2_2") (pintype "passive"))
      (node (ref "J15") (pin "2") (pinfunction "P2_2") (pintype "passive"))
      (node (ref "J16") (pin "2") (pinfunction "P2_2") (pintype "passive"))
      (node (ref "J17") (pin "2") (pinfunction "P2_2") (pintype "passive"))
      (node (ref "J18") (pin "5") (pinfunction "P5_5") (pintype "passive"))
      (node (ref "J19") (pin "2") (pinfunction "P2_2") (pintype "passive"))
      (node (ref "J2") (pin "2") (pinfunction "P2_2") (pintype "passive"))
      (node (ref "J20") (pin "2") (pinfunction "P2_2") (pintype "passive"))
      (node (ref "J21") (pin "3") (pinfunction "P3_3") (pintype "passive"))
      (node (ref "J22") (pin "3") (pinfunction "P3_3") (pintype "passive"))
      (node (ref "J23") (pin "2") (pinfunction "P2_2") (pintype "passive"))
      (node (ref "J24") (pin "2") (pinfunction "P2_2") (pintype "passive"))
      (node (ref "J26") (pin "4") (pinfunction "P4_4") (pintype "passive"))
      (node (ref "J27") (pin "4") (pinfunction "P4_4") (pintype "passive"))
      (node (ref "J3") (pin "5") (pinfunction "P5_5") (pintype "passive"))
      (node (ref "J34") (pin "4") (pinfunction "P4_4") (pintype "passive"))
      (node (ref "J4") (pin "4") (pinfunction "P4_4") (pintype "passive"))
      (node (ref "J5") (pin "4") (pinfunction "P4_4") (pintype "passive"))
      (node (ref "J7") (pin "1") (pinfunction "P1_1") (pintype "passive"))
      (node (ref "J7") (pin "2") (pinfunction "P2_2") (pintype "passive"))
      (node (ref "J7") (pin "3") (pinfunction "P3_3") (pintype "passive"))
      (node (ref "J7") (pin "4") (pinfunction "P4_4") (pintype "passive"))
      (node (ref "J7") (pin "5") (pinfunction "P5_5") (pintype "passive"))
      (node (ref "R5") (pin "1") (pinfunction "A_1") (pintype "passive"))
      (node (ref "U1") (pin "2") (pinfunction "GND_2") (pintype "passive"))
      (node (ref "U2") (pin "3") (pinfunction "GND_3") (pintype "passive"))
      (node (ref "U3") (pin "11") (pinfunction "GND_11") (pintype "passive"))
      (node (ref "U3") (pin "32") (pinfunction "GND_32") (pintype "passive"))
      (node (ref "U3") (pin "62") (pinfunction "GND_62") (pintype "passive"))
      (node (ref "U3") (pin "81") (pinfunction "GND_81") (pintype "passive"))
      (node (ref "U3") (pin "99") (pinfunction "AGND_99") (pintype "passive"))
      (node (ref "U4") (pin "1") (pinfunction "GND_1") (pintype "passive"))
      (node (ref "U7") (pin "3") (pinfunction "GND_3") (pintype "passive"))
    )
    (net (code "55") (name "Net-(LD1-K)") (class "Default")
      (node (ref "LD1") (pin "1") (pinfunction "K_1") (pintype "passive"))
      (node (ref "R5") (pin "2") (pinfunction "B_2") (pintype "passive"))
    )
    (net (code "56") (name "Net-(LD2-K)") (class "Default")
      (node (ref "LD2") (pin "1") (pinfunction "K_1") (pintype "passive"))
      (node (ref "R6") (pin "2") (pinfunction "B_2") (pintype "passive"))
    )
    (net (code "57") (name "Net-(LD3-K)") (class "Default")
      (node (ref "LD3") (pin "1") (pinfunction "K_1") (pintype "passive"))
      (node (ref "R7") (pin "2") (pinfunction "B_2") (pintype "passive"))
    )
    (net (code "58") (name "Net-(U7-CAP)") (class "Default")
      (node (ref "C15") (pin "1") (pinfunction "1_1") (pintype "passive"))
      (node (ref "U7") (pin "2") (pinfunction "CAP_2") (pintype "passive"))
    )
    (net (code "59") (name "unconnected-(U3-(AD2)PA2-Pad76)") (class "Default")
      (node (ref "U3") (pin "76") (pinfunction "(AD2)PA2_76") (pintype "passive"))
    )
    (net (code "60") (name "unconnected-(U3-(AD3)PA3-Pad75)") (class "Default")
      (node (ref "U3") (pin "75") (pinfunction "(AD3)PA3_75") (pintype "passive"))
    )
    (net (code "61") (name "unconnected-(U3-(AD4)PA4-Pad74)") (class "Default")
      (node (ref "U3") (pin "74") (pinfunction "(AD4)PA4_74") (pintype "passive"))
    )
    (net (code "62") (name "unconnected-(U3-(AD5)PA5-Pad73)") (class "Default")
      (node (ref "U3") (pin "73") (pinfunction "(AD5)PA5_73") (pintype "passive"))
    )
    (net (code "63") (name "unconnected-(U3-(AD6)PA6-Pad72)") (class "Default")
      (node (ref "U3") (pin "72") (pinfunction "(AD6)PA6_72") (pintype "passive"))
    )
    (net (code "64") (name "unconnected-(U3-(AD7)PA7-Pad71)") (class "Default")
      (node (ref "U3") (pin "71") (pinfunction "(AD7)PA7_71") (pintype "passive"))
    )
    (net (code "65") (name "unconnected-(U3-(ADC7{slash}TDI)PF7-Pad90)") (class "Default")
      (node (ref "U3") (pin "90") (pinfunction "(ADC7/TDI)PF7_90") (pintype "passive+no_connect"))
    )
    (net (code "66") (name "unconnected-(U3-(ALE)PG2-Pad70)") (class "Default")
      (node (ref "U3") (pin "70") (pinfunction "(ALE)PG2_70") (pintype "passive+no_connect"))
    )
    (net (code "67") (name "unconnected-(U3-(CLKO{slash}ICP3{slash}INT7)PE7-Pad9)") (class "Default")
      (node (ref "U3") (pin "9") (pinfunction "(CLKO/ICP3/INT7)PE7_9") (pintype "passive+no_connect"))
    )
    (net (code "68") (name "unconnected-(U3-(ICP1)PD4-Pad47)") (class "Default")
      (node (ref "U3") (pin "47") (pinfunction "(ICP1)PD4_47") (pintype "passive+no_connect"))
    )
    (net (code "69") (name "unconnected-(U3-(OC0B)PG5-Pad1)") (class "Default")
      (node (ref "U3") (pin "1") (pinfunction "(OC0B)PG5_1") (pintype "passive+no_connect"))
    )
    (net (code "70") (name "unconnected-(U3-(OC3B{slash}INT4)PE4-Pad6)") (class "Default")
      (node (ref "U3") (pin "6") (pinfunction "(OC3B/INT4)PE4_6") (pintype "passive+no_connect"))
    )
    (net (code "71") (name "unconnected-(U3-(OC3C{slash}INT5)PE5-Pad7)") (class "Default")
      (node (ref "U3") (pin "7") (pinfunction "(OC3C/INT5)PE5_7") (pintype "passive+no_connect"))
    )
    (net (code "72") (name "unconnected-(U3-(T0)PD7-Pad50)") (class "Default")
      (node (ref "U3") (pin "50") (pinfunction "(T0)PD7_50") (pintype "passive+no_connect"))
    )
    (net (code "73") (name "unconnected-(U3-(T1)PD6-Pad49)") (class "Default")
      (node (ref "U3") (pin "49") (pinfunction "(T1)PD6_49") (pintype "passive+no_connect"))
    )
    (net (code "74") (name "unconnected-(U3-(T3{slash}INT6)PE6-Pad8)") (class "Default")
      (node (ref "U3") (pin "8") (pinfunction "(T3/INT6)PE6_8") (pintype "passive+no_connect"))
    )
    (net (code "75") (name "unconnected-(U3-(TOSC1)PG4-Pad29)") (class "Default")
      (node (ref "U3") (pin "29") (pinfunction "(TOSC1)PG4_29") (pintype "passive+no_connect"))
    )
    (net (code "76") (name "unconnected-(U3-(TOSC2)PG3-Pad28)") (class "Default")
      (node (ref "U3") (pin "28") (pinfunction "(TOSC2)PG3_28") (pintype "passive+no_connect"))
    )
    (net (code "77") (name "unconnected-(U3-(XCK0{slash}AIN0)PE2-Pad4)") (class "Default")
      (node (ref "U3") (pin "4") (pinfunction "(XCK0/AIN0)PE2_4") (pintype "passive+no_connect"))
    )
    (net (code "78") (name "unconnected-(U3-(XCK1)PD5-Pad48)") (class "Default")
      (node (ref "U3") (pin "48") (pinfunction "(XCK1)PD5_48") (pintype "passive+no_connect"))
    )
    (net (code "79") (name "unconnected-(U3-PH2(XCK2)-Pad14)") (class "Default")
      (node (ref "U3") (pin "14") (pinfunction "PH2(XCK2)_14") (pintype "passive+no_connect"))
    )
    (net (code "80") (name "unconnected-(U3-PH7(T4)-Pad27)") (class "Default")
      (node (ref "U3") (pin "27") (pinfunction "PH7(T4)_27") (pintype "passive+no_connect"))
    )
    (net (code "81") (name "unconnected-(U3-PJ2(XCK3{slash}PCINT11)-Pad65)") (class "Default")
      (node (ref "U3") (pin "65") (pinfunction "PJ2(XCK3/PCINT11)_65") (pintype "passive+no_connect"))
    )
    (net (code "82") (name "unconnected-(U3-PJ5(PCINT14)-Pad68)") (class "Default")
      (node (ref "U3") (pin "68") (pinfunction "PJ5(PCINT14)_68") (pintype "passive+no_connect"))
    )
    (net (code "83") (name "unconnected-(U3-PJ6(PCINT15)-Pad69)") (class "Default")
      (node (ref "U3") (pin "69") (pinfunction "PJ6(PCINT15)_69") (pintype "passive+no_connect"))
    )
    (net (code "84") (name "unconnected-(U3-PJ7-Pad79)") (class "Default")
      (node (ref "U3") (pin "79") (pinfunction "PJ7_79") (pintype "passive+no_connect"))
    )
    (net (code "85") (name "unconnected-(U3-PK0(ADC8{slash}PCINT16)-Pad89)") (class "Default")
      (node (ref "U3") (pin "89") (pinfunction "PK0(ADC8/PCINT16)_89") (pintype "passive+no_connect"))
    )
    (net (code "86") (name "unconnected-(U3-PK1(ADC9{slash}PCINT17)-Pad88)") (class "Default")
      (node (ref "U3") (pin "88") (pinfunction "PK1(ADC9/PCINT17)_88") (pintype "passive+no_connect"))
    )
    (net (code "87") (name "unconnected-(U3-PK2(ADC10{slash}PCINT18)-Pad87)") (class "Default")
      (node (ref "U3") (pin "87") (pinfunction "PK2(ADC10/PCINT18)_87") (pintype "passive+no_connect"))
    )
    (net (code "88") (name "unconnected-(U3-PK3(ADC11{slash}PCINT19)-Pad86)") (class "Default")
      (node (ref "U3") (pin "86") (pinfunction "PK3(ADC11/PCINT19)_86") (pintype "passive+no_connect"))
    )
    (net (code "89") (name "unconnected-(U3-PK4(ADC12{slash}PCINT20)-Pad85)") (class "Default")
      (node (ref "U3") (pin "85") (pinfunction "PK4(ADC12/PCINT20)_85") (pintype "passive+no_connect"))
    )
    (net (code "90") (name "unconnected-(U3-PK5(ADC13{slash}PCINT21)-Pad84)") (class "Default")
      (node (ref "U3") (pin "84") (pinfunction "PK5(ADC13/PCINT21)_84") (pintype "passive+no_connect"))
    )
    (net (code "91") (name "unconnected-(U3-PK6(ADC14{slash}PCINT22)-Pad83)") (class "Default")
      (node (ref "U3") (pin "83") (pinfunction "PK6(ADC14/PCINT22)_83") (pintype "passive+no_connect"))
    )
    (net (code "92") (name "unconnected-(U3-PK7(ADC15{slash}PCINT23)-Pad82)") (class "Default")
      (node (ref "U3") (pin "82") (pinfunction "PK7(ADC15/PCINT23)_82") (pintype "passive+no_connect"))
    )
    (net (code "93") (name "unconnected-(U3-PL0(ICP4)-Pad35)") (class "Default")
      (node (ref "U3") (pin "35") (pinfunction "PL0(ICP4)_35") (pintype "passive+no_connect"))
    )
    (net (code "94") (name "unconnected-(U3-PL1(ICP5)-Pad36)") (class "Default")
      (node (ref "U3") (pin "36") (pinfunction "PL1(ICP5)_36") (pintype "passive+no_connect"))
    )
    (net (code "95") (name "unconnected-(U3-PL2(T5)-Pad37)") (class "Default")
      (node (ref "U3") (pin "37") (pinfunction "PL2(T5)_37") (pintype "passive+no_connect"))
    )
    (net (code "96") (name "unconnected-(U3-PL3(OC5A)-Pad38)") (class "Default")
      (node (ref "U3") (pin "38") (pinfunction "PL3(OC5A)_38") (pintype "passive+no_connect"))
    )
    (net (code "97") (name "unconnected-(U3-PL6-Pad41)") (class "Default")
      (node (ref "U3") (pin "41") (pinfunction "PL6_41") (pintype "passive+no_connect"))
    )
    (net (code "98") (name "unconnected-(U3-PL7-Pad42)") (class "Default")
      (node (ref "U3") (pin "42") (pinfunction "PL7_42") (pintype "passive+no_connect"))
    )
    (net (code "99") (name "unconnected-(U7-INT_1-Pad6)") (class "Default")
      (node (ref "U7") (pin "6") (pinfunction "INT_1_6") (pintype "passive+no_connect"))
    )
    (net (code "100") (name "unconnected-(U7-INT_2-Pad5)") (class "Default")
      (node (ref "U7") (pin "5") (pinfunction "INT_2_5") (pintype "passive+no_connect"))
    )
  )
)
